# tmp235_Front_End_Siognal_Chain.net
KiCad netlist of a schematic drawn in Altium Designer
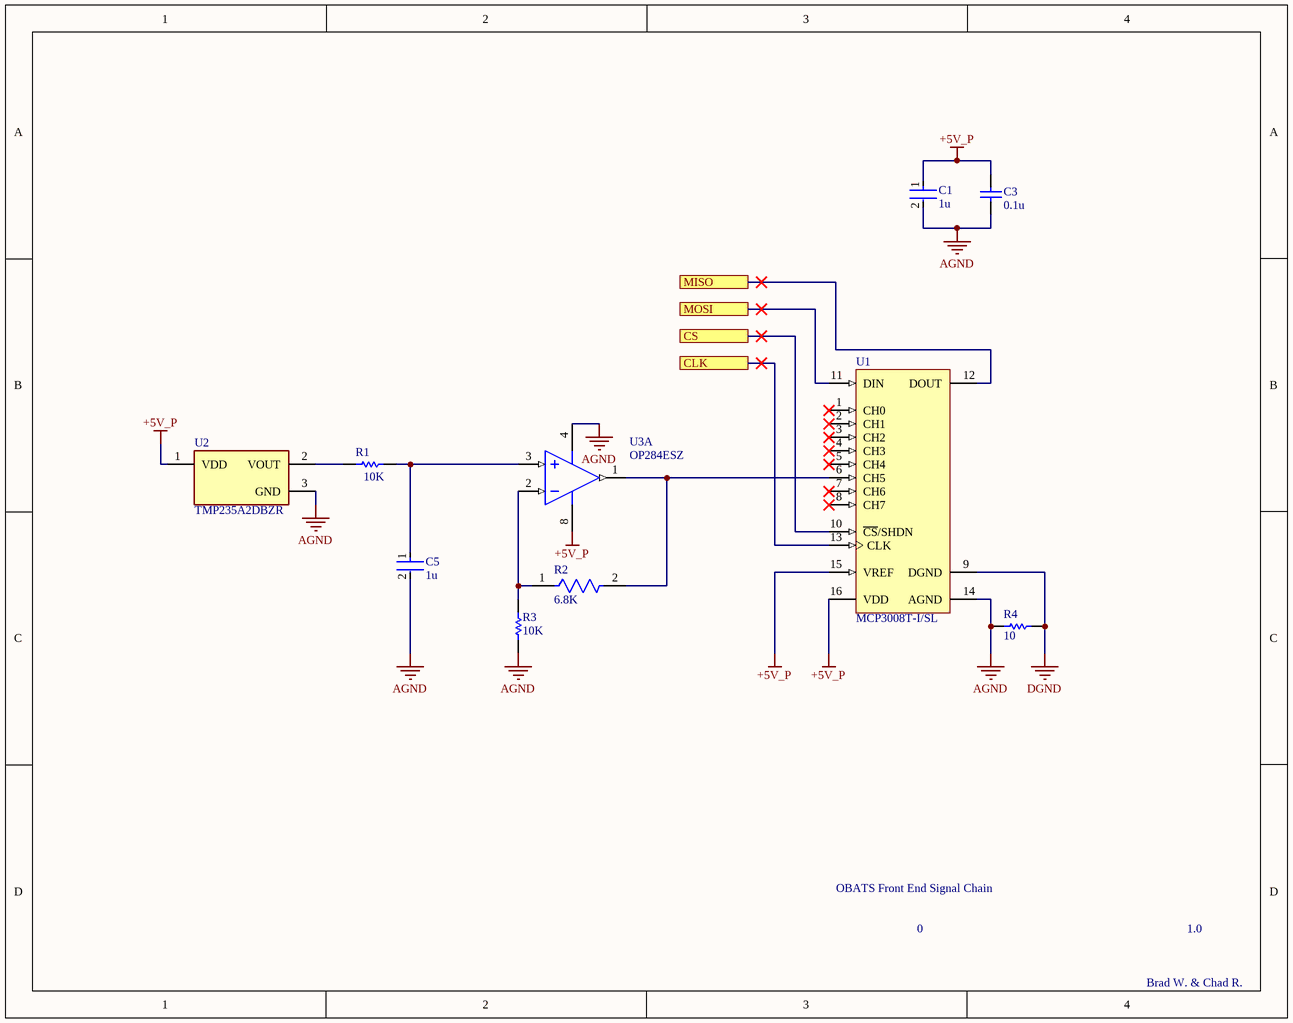
[diagram p0: tmp235_Front_End_Siognal_Chain.SchDoc]

(export (version "E")
  (design (tool "Eeschema 10.0.6"))
  (components
    (comp (ref "C1")
      (value "1u")
      (footprint "FP-CL31-IPC_B")
      (description "Cap Ceramic 1uF 50V X7R ±10% SMD 1206 +125°C Embossed T/R")
      (fields (field (name "VOLTAGE") "50V") (field (name "TOLERANCE") "10%"))
      (libsource (lib "Altium Content Vault") (part "b4654b650e69147ec39a6b967a45e02"))
    )
    (comp (ref "C3")
      (value "0.1u")
      (footprint "CAPC1206(3216)130_M")
      (description "CAP 100nF 100V ±20% 1206 (3216 Metric) Thickness 1.3mm SMD")
      (fields (field (name "TOLERANCE") "Â±20%"))
      (libsource (lib "Altium Content Vault") (part "CAP"))
    )
    (comp (ref "C5")
      (value "1u")
      (footprint "FP-CL31-IPC_B")
      (description "Cap Ceramic 1uF 50V X7R ±10% SMD 1206 +125°C Embossed T/R")
      (fields (field (name "VOLTAGE") "50V") (field (name "TOLERANCE") "10%"))
      (libsource (lib "Altium Content Vault") (part "b4654b650e69147ec39a6b967a45e02"))
    )
    (comp (ref "R1")
      (value "10K")
      (footprint "RESC3116X65X45ML10T20")
      (fields (field (name "MANUFACTURER") "Yageo") (field (name "PART NUMBER") "AC1206FR-0710KL"))
      (libsource (lib "Altium Content Vault") (part "RES"))
    )
    (comp (ref "R2")
      (value "6.8K")
      (footprint "FP-AC1206-MFG")
      (description "RES SMD 6.8K OHM 1% 1/4W 1206")
      (fields
        (field (name "OCTOPART") "https://octopart.com/ac1206fr-076k8l-yageo-26041203")
        (field (name "MANUFACTURER PART NUMBER") "AC1206FR-076K8L")
      )
      (libsource (lib "Altium Content Vault") (part "1029c3af85768c4190bb7ad29bc67b5"))
    )
    (comp (ref "R3")
      (value "10K")
      (footprint "RESC3116X65X45ML10T20")
      (fields (field (name "MANUFACTURER") "Yageo") (field (name "PART NUMBER") "AC1206FR-0710KL"))
      (libsource (lib "Altium Content Vault") (part "RES"))
    )
    (comp (ref "R4")
      (value "10")
      (footprint "RESC3216X60X45ML10T20")
      (fields (field (name "MANUFACTURER") "Vishay Dale") (field (name "PART NUMBER") "CRCW120610R0FKEA"))
      (libsource (lib "Altium Content Vault") (part "RES"))
    )
    (comp (ref "U1")
      (value "MCP3008T-I/SL")
      (footprint "SOIC-SL16_N")
      (libsource (lib "Altium Content Vault") (part "CON-ADC-MCP3008-16"))
    )
    (comp (ref "U2")
      (value "TMP235A2DBZR")
      (footprint "FP-DBZ0003A-MFG")
      (description "LOW-POWER HIGH-ACCURACY ANALOG O")
      (fields
        (field (name "MANUFACTURER") "Texas Instruments")
        (field (name "OCTOPART") "https://octopart.com/tmp235a2dbzr-texas+instruments-94966376")
      )
      (libsource (lib "Altium Content Vault") (part "1212246baba8f64ab0dd7b63bd818eb"))
    )
    (comp (ref "U3")
      (value "OP284ESZ")
      (footprint "ADI-R-8_L")
      (fields (field (name "GENERIC PART NUMBER") "OP284") (field (name "MANUFACTURER") "Analog Devices"))
      (libsource (lib "Altium Content Vault") (part "ADI-OP29X-R-8"))
    )
  )
  (nets
    (net (code "1") (name "+5V_P") (class "Default")
      (node (ref "C1") (pin "1") (pinfunction "1_1") (pintype "passive"))
      (node (ref "C3") (pin "2") (pinfunction "2_2") (pintype "passive"))
      (node (ref "U1") (pin "15") (pinfunction "VREF_15") (pintype "input"))
      (node (ref "U1") (pin "16") (pinfunction "VDD_16") (pintype "power_in"))
      (node (ref "U2") (pin "1") (pinfunction "VDD_1") (pintype "power_in"))
      (node (ref "U3") (pin "8") (pinfunction "+V_8") (pintype "power_in"))
    )
    (net (code "2") (name "/CLK") (class "Default")
      (node (ref "U1") (pin "13") (pinfunction "CLK_13") (pintype "input"))
    )
    (net (code "3") (name "/CS") (class "Default")
      (node (ref "U1") (pin "10") (pinfunction "~{CS}/SHDN_10") (pintype "input"))
    )
    (net (code "4") (name "/MISO") (class "Default")
      (node (ref "U1") (pin "12") (pinfunction "DOUT_12") (pintype "tri_state"))
    )
    (net (code "5") (name "/MOSI") (class "Default")
      (node (ref "U1") (pin "11") (pinfunction "DIN_11") (pintype "input"))
    )
    (net (code "6") (name "AGND") (class "Default")
      (node (ref "C1") (pin "2") (pinfunction "2_2") (pintype "passive"))
      (node (ref "C3") (pin "1") (pinfunction "1_1") (pintype "passive"))
      (node (ref "C5") (pin "2") (pinfunction "2_2") (pintype "passive"))
      (node (ref "R3") (pin "1") (pinfunction "1_1") (pintype "passive"))
      (node (ref "R4") (pin "1") (pinfunction "1_1") (pintype "passive"))
      (node (ref "U1") (pin "14") (pinfunction "AGND_14") (pintype "power_in"))
      (node (ref "U2") (pin "3") (pinfunction "GND_3") (pintype "power_in"))
      (node (ref "U3") (pin "4") (pinfunction "-V_4") (pintype "power_in"))
    )
    (net (code "7") (name "DGND") (class "Default")
      (node (ref "R4") (pin "2") (pinfunction "2_2") (pintype "passive"))
      (node (ref "U1") (pin "9") (pinfunction "DGND_9") (pintype "power_in"))
    )
    (net (code "8") (name "Net-(U1-CH5)") (class "Default")
      (node (ref "R2") (pin "2") (pinfunction "2_2") (pintype "passive"))
      (node (ref "U1") (pin "6") (pinfunction "CH5_6") (pintype "input"))
      (node (ref "U3") (pin "1") (pinfunction "OUT_A_1") (pintype "output"))
    )
    (net (code "9") (name "Net-(U2-VOUT)") (class "Default")
      (node (ref "R1") (pin "1") (pinfunction "1_1") (pintype "passive"))
      (node (ref "U2") (pin "2") (pinfunction "VOUT_2") (pintype "passive"))
    )
    (net (code "10") (name "Net-(U3A-+IN_A)") (class "Default")
      (node (ref "C5") (pin "1") (pinfunction "1_1") (pintype "passive"))
      (node (ref "R1") (pin "2") (pinfunction "2_2") (pintype "passive"))
      (node (ref "U3") (pin "3") (pinfunction "+IN_A_3") (pintype "input"))
    )
    (net (code "11") (name "Net-(U3A--IN_A)") (class "Default")
      (node (ref "R2") (pin "1") (pinfunction "1_1") (pintype "passive"))
      (node (ref "R3") (pin "2") (pinfunction "2_2") (pintype "passive"))
      (node (ref "U3") (pin "2") (pinfunction "-IN_A_2") (pintype "input"))
    )
    (net (code "12") (name "unconnected-(U1-CH0-Pad1)") (class "Default")
      (node (ref "U1") (pin "1") (pinfunction "CH0_1") (pintype "input+no_connect"))
    )
    (net (code "13") (name "unconnected-(U1-CH1-Pad2)") (class "Default")
      (node (ref "U1") (pin "2") (pinfunction "CH1_2") (pintype "input+no_connect"))
    )
    (net (code "14") (name "unconnected-(U1-CH2-Pad3)") (class "Default")
      (node (ref "U1") (pin "3") (pinfunction "CH2_3") (pintype "input+no_connect"))
    )
    (net (code "15") (name "unconnected-(U1-CH3-Pad4)") (class "Default")
      (node (ref "U1") (pin "4") (pinfunction "CH3_4") (pintype "input+no_connect"))
    )
    (net (code "16") (name "unconnected-(U1-CH4-Pad5)") (class "Default")
      (node (ref "U1") (pin "5") (pinfunction "CH4_5") (pintype "input+no_connect"))
    )
    (net (code "17") (name "unconnected-(U1-CH6-Pad7)") (class "Default")
      (node (ref "U1") (pin "7") (pinfunction "CH6_7") (pintype "input+no_connect"))
    )
    (net (code "18") (name "unconnected-(U1-CH7-Pad8)") (class "Default")
      (node (ref "U1") (pin "8") (pinfunction "CH7_8") (pintype "input+no_connect"))
    )
  )
)
